# glowhacker_rev_a.net
KiCad netlist of a schematic drawn in EAGLE
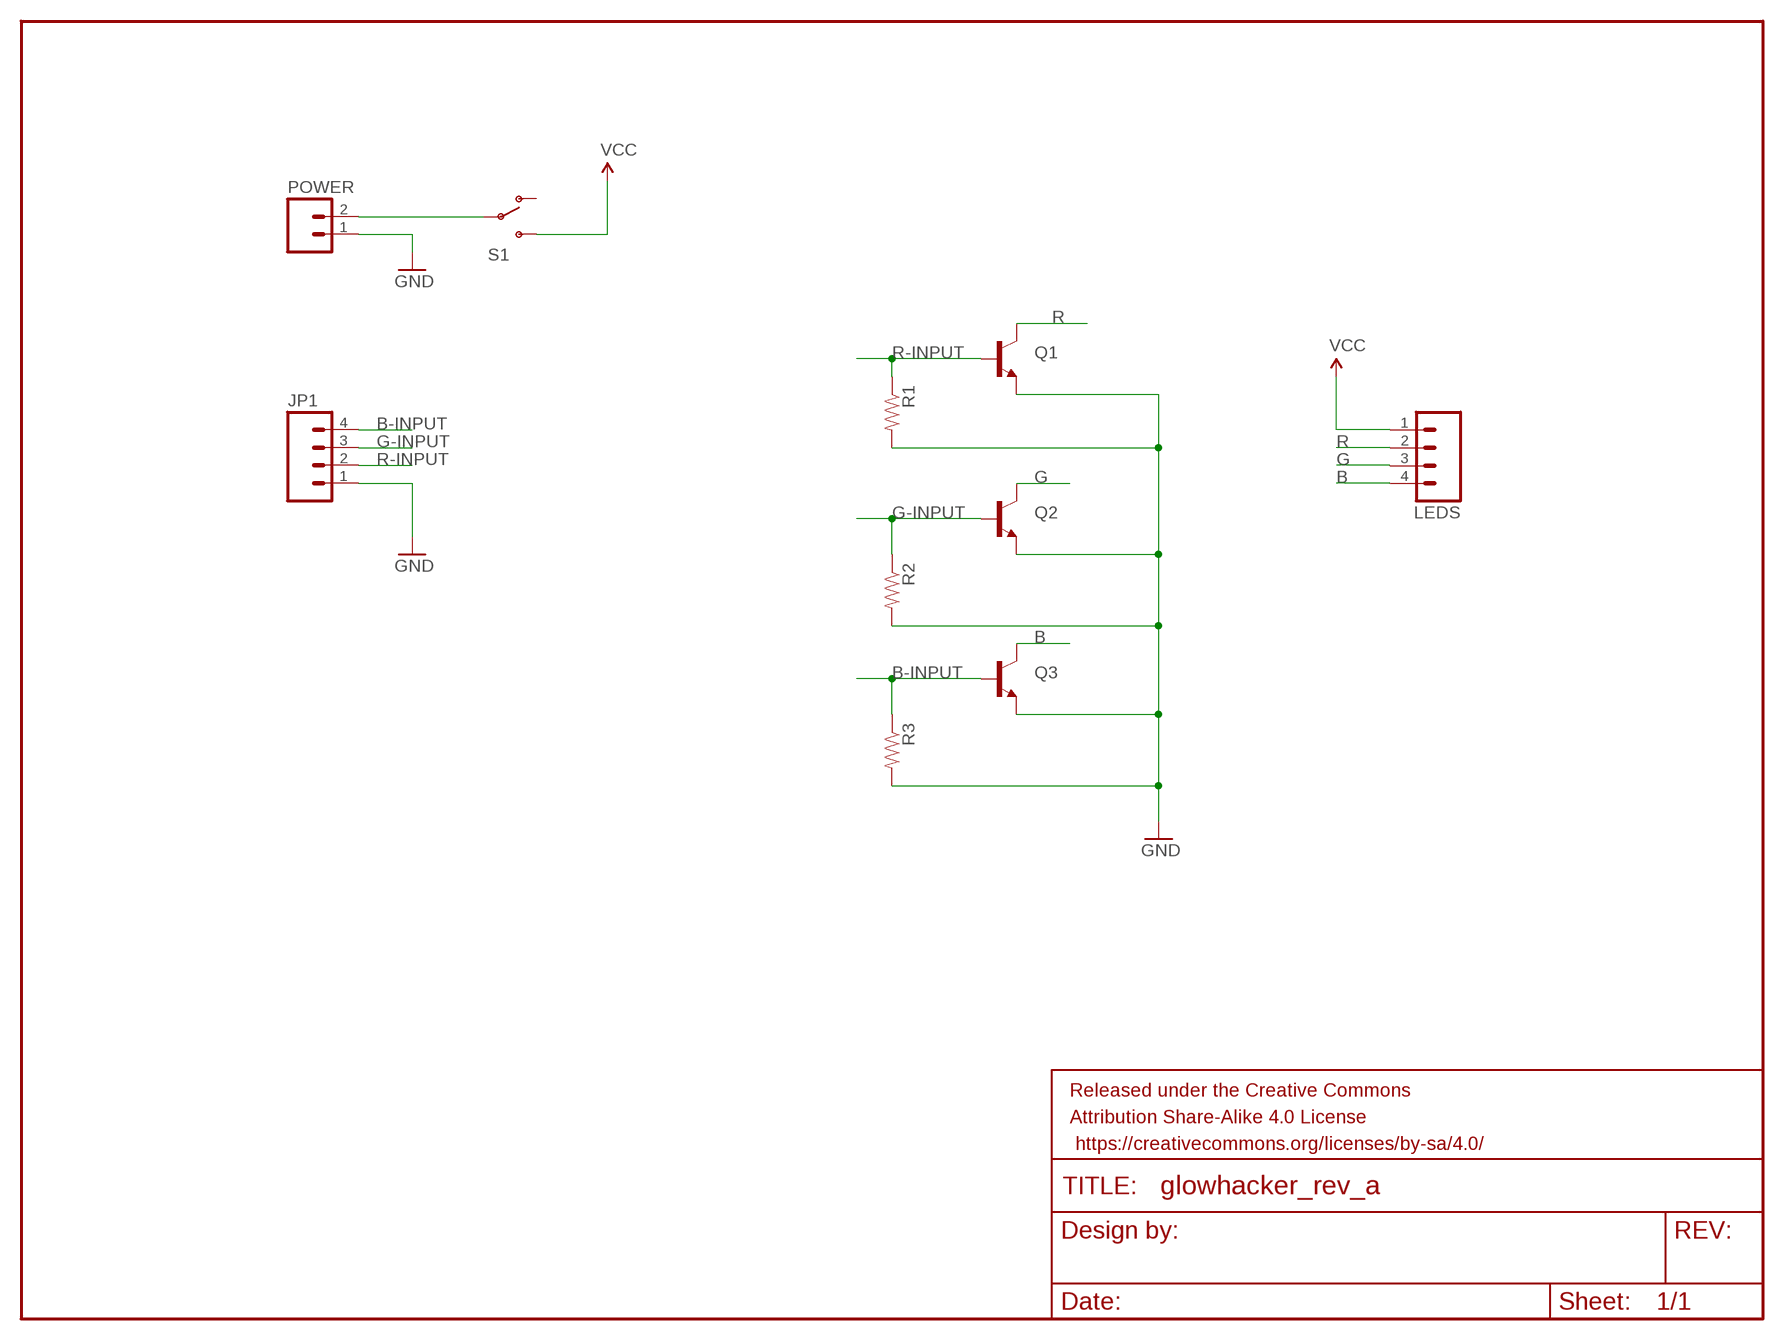
[diagram p0: schematic, sheet 1]

(export (version "E")
  (design (tool "Eeschema 10.0.6"))
  (components
    (comp (ref "FRAME1")
      (value "FRAME-LETTER")
      (footprint "eagle-import:CREATIVE_COMMONS")
      (libsource (lib "eagle-import") (part "FRAME-LETTER"))
    )
    (comp (ref "JP1")
      (value "M04PTH")
      (footprint "eagle-import:1X04")
      (libsource (lib "eagle-import") (part "M04PTH"))
    )
    (comp (ref "LEDS")
      (value "M04PTH")
      (footprint "eagle-import:1X04")
      (libsource (lib "eagle-import") (part "M04PTH"))
    )
    (comp (ref "POWER")
      (value "M02PTH")
      (footprint "eagle-import:1X02")
      (libsource (lib "eagle-import") (part "M02PTH"))
    )
    (comp (ref "Q1")
      (value "TRANSISTOR_NPNTO-92-AMMO")
      (footprint "eagle-import:TO-92-AMMO")
      (libsource (lib "eagle-import") (part "TRANSISTOR_NPNTO-92-AMMO"))
    )
    (comp (ref "Q2")
      (value "TRANSISTOR_NPNTO-92-AMMO")
      (footprint "eagle-import:TO-92-AMMO")
      (libsource (lib "eagle-import") (part "TRANSISTOR_NPNTO-92-AMMO"))
    )
    (comp (ref "Q3")
      (value "TRANSISTOR_NPNTO-92-AMMO")
      (footprint "eagle-import:TO-92-AMMO")
      (libsource (lib "eagle-import") (part "TRANSISTOR_NPNTO-92-AMMO"))
    )
    (comp (ref "R1")
      (value "RESISTOREZ")
      (footprint "eagle-import:AXIAL-0.3EZ")
      (libsource (lib "eagle-import") (part "RESISTOREZ"))
    )
    (comp (ref "R2")
      (value "RESISTOREZ")
      (footprint "eagle-import:AXIAL-0.3EZ")
      (libsource (lib "eagle-import") (part "RESISTOREZ"))
    )
    (comp (ref "R3")
      (value "RESISTOREZ")
      (footprint "eagle-import:AXIAL-0.3EZ")
      (libsource (lib "eagle-import") (part "RESISTOREZ"))
    )
    (comp (ref "S1")
      (value "SWITCH-SPDTPTH")
      (footprint "eagle-import:SWITCH-SPDT")
      (libsource (lib "eagle-import") (part "SWITCH-SPDTPTH"))
    )
  )
  (nets
    (net (code "1") (name "/B") (class "Default")
      (node (ref "LEDS") (pin "4") (pinfunction "4_4") (pintype "passive"))
      (node (ref "Q3") (pin "3") (pinfunction "C_3") (pintype "passive"))
    )
    (net (code "2") (name "/B-INPUT") (class "Default")
      (node (ref "JP1") (pin "4") (pinfunction "4_4") (pintype "passive"))
      (node (ref "Q3") (pin "2") (pinfunction "B_2") (pintype "passive"))
      (node (ref "R3") (pin "P$1") (pinfunction "1_P$1") (pintype "passive"))
    )
    (net (code "3") (name "/G") (class "Default")
      (node (ref "LEDS") (pin "3") (pinfunction "3_3") (pintype "passive"))
      (node (ref "Q2") (pin "3") (pinfunction "C_3") (pintype "passive"))
    )
    (net (code "4") (name "/G-INPUT") (class "Default")
      (node (ref "JP1") (pin "3") (pinfunction "3_3") (pintype "passive"))
      (node (ref "Q2") (pin "2") (pinfunction "B_2") (pintype "passive"))
      (node (ref "R2") (pin "P$1") (pinfunction "1_P$1") (pintype "passive"))
    )
    (net (code "5") (name "/R") (class "Default")
      (node (ref "LEDS") (pin "2") (pinfunction "2_2") (pintype "passive"))
      (node (ref "Q1") (pin "3") (pinfunction "C_3") (pintype "passive"))
    )
    (net (code "6") (name "/R-INPUT") (class "Default")
      (node (ref "JP1") (pin "2") (pinfunction "2_2") (pintype "passive"))
      (node (ref "Q1") (pin "2") (pinfunction "B_2") (pintype "passive"))
      (node (ref "R1") (pin "P$1") (pinfunction "1_P$1") (pintype "passive"))
    )
    (net (code "7") (name "GND") (class "Default")
      (node (ref "JP1") (pin "1") (pinfunction "1_1") (pintype "passive"))
      (node (ref "POWER") (pin "1") (pinfunction "1_1") (pintype "passive"))
      (node (ref "Q1") (pin "1") (pinfunction "E_1") (pintype "passive"))
      (node (ref "Q2") (pin "1") (pinfunction "E_1") (pintype "passive"))
      (node (ref "Q3") (pin "1") (pinfunction "E_1") (pintype "passive"))
      (node (ref "R1") (pin "P$2") (pinfunction "2_P$2") (pintype "passive"))
      (node (ref "R2") (pin "P$2") (pinfunction "2_P$2") (pintype "passive"))
      (node (ref "R3") (pin "P$2") (pinfunction "2_P$2") (pintype "passive"))
    )
    (net (code "8") (name "Net-(S1-P)") (class "Default")
      (node (ref "POWER") (pin "2") (pinfunction "2_2") (pintype "passive"))
      (node (ref "S1") (pin "2") (pinfunction "P_2") (pintype "passive"))
    )
    (net (code "9") (name "VCC") (class "Default")
      (node (ref "LEDS") (pin "1") (pinfunction "1_1") (pintype "passive"))
      (node (ref "S1") (pin "3") (pinfunction "S_3") (pintype "passive"))
    )
    (net (code "10") (name "unconnected-(S1-O-Pad1)") (class "Default")
      (node (ref "S1") (pin "1") (pinfunction "O_1") (pintype "passive"))
    )
  )
)
